# ASD2116.net
KiCad netlist of a schematic drawn in EAGLE
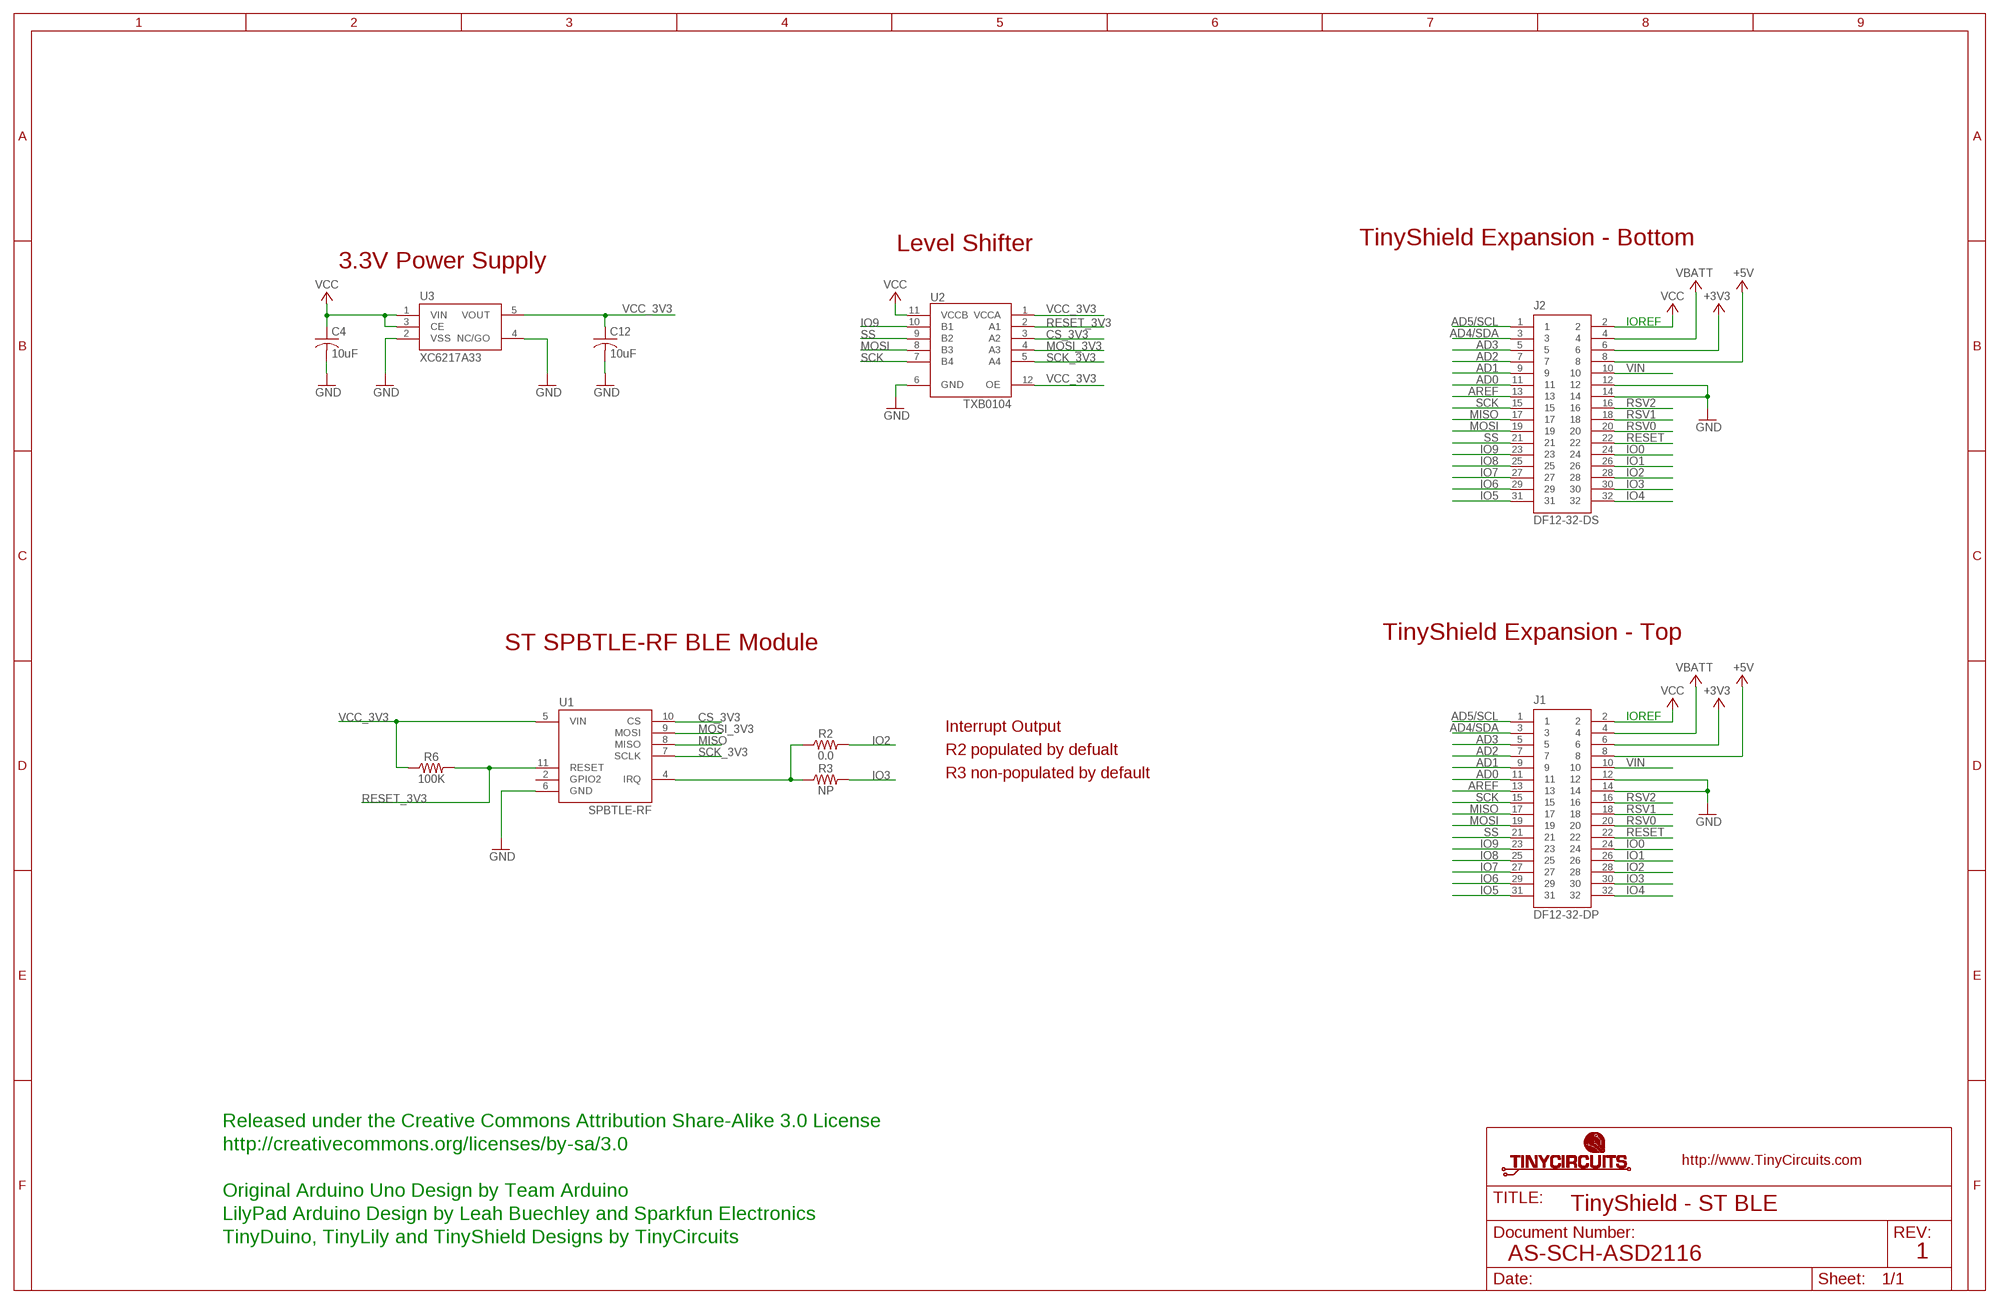
[diagram p0: schematic, sheet 1]

(export (version "E")
  (design (tool "Eeschema 10.0.6"))
  (components
    (comp (ref "C4")
      (value "10uF")
      (footprint "eagle-import:C0603")
      (fields (field (name "PARTNO") "AS-ITM-00002") (field (name "PARTNO_1") "AS-ITM-00002"))
      (libsource (lib "eagle-import") (part "AS-ITM-00002"))
    )
    (comp (ref "C12")
      (value "10uF")
      (footprint "eagle-import:C0603")
      (fields (field (name "PARTNO") "AS-ITM-00002") (field (name "PARTNO_1") "AS-ITM-00002"))
      (libsource (lib "eagle-import") (part "AS-ITM-00002"))
    )
    (comp (ref "J1")
      (value "DF12-32-DP")
      (footprint "eagle-import:DF12-32-DP")
      (fields (field (name "PARTNO") "AS-ITM-00015") (field (name "PARTNO_1") "AS-ITM-00015"))
      (libsource (lib "eagle-import") (part "AS-ITM-00015"))
    )
    (comp (ref "J2")
      (value "DF12-32-DS")
      (footprint "eagle-import:DF12-32-DS")
      (fields (field (name "PARTNO") "AS-ITM-00012") (field (name "PARTNO_1") "AS-ITM-00012"))
      (libsource (lib "eagle-import") (part "AS-ITM-00012"))
    )
    (comp (ref "R2")
      (value "0.0")
      (footprint "eagle-import:0402")
      (fields (field (name "PARTNO") "AS-ITM-00076") (field (name "PARTNO_1") "AS-ITM-00076"))
      (libsource (lib "eagle-import") (part "AS-ITM-00076"))
    )
    (comp (ref "R3")
      (value "NP")
      (footprint "eagle-import:0402")
      (fields (field (name "PARTNO") "AS-ITM-00076") (field (name "PARTNO_1") "AS-ITM-00076"))
      (libsource (lib "eagle-import") (part "AS-ITM-00076"))
    )
    (comp (ref "R6")
      (value "100K")
      (footprint "eagle-import:0402")
      (fields (field (name "PARTNO") "AS-ITM-00004"))
      (libsource (lib "eagle-import") (part "AS-ITM-00004"))
    )
    (comp (ref "U1")
      (value "SPBTLE-RF")
      (footprint "eagle-import:SPBTLE-RF")
      (fields (field (name "PARTNO") "AS-ITM-00294"))
      (libsource (lib "eagle-import") (part "AS-ITM-00294"))
    )
    (comp (ref "U2")
      (value "TXB0104")
      (footprint "eagle-import:UQFN-12")
      (fields (field (name "PARTNO") "AS-ITM-00048"))
      (libsource (lib "eagle-import") (part "AS-ITM-00048"))
    )
    (comp (ref "U3")
      (value "XC6217A33")
      (footprint "eagle-import:SOT-25")
      (fields (field (name "PARTNO") "AS-ITM-00249") (field (name "PARTNO_1") "AS-ITM-00249"))
      (libsource (lib "eagle-import") (part "AS-ITM-00249"))
    )
  )
  (nets
    (net (code "1") (name "+3V3") (class "Default")
      (node (ref "J1") (pin "6") (pinfunction "6_6") (pintype "bidirectional"))
      (node (ref "J2") (pin "6") (pinfunction "6_6") (pintype "bidirectional"))
    )
    (net (code "2") (name "+5V") (class "Default")
      (node (ref "J1") (pin "8") (pinfunction "8_8") (pintype "bidirectional"))
      (node (ref "J2") (pin "8") (pinfunction "8_8") (pintype "bidirectional"))
    )
    (net (code "3") (name "/AD0") (class "Default")
      (node (ref "J1") (pin "11") (pinfunction "11_11") (pintype "bidirectional"))
      (node (ref "J2") (pin "11") (pinfunction "11_11") (pintype "bidirectional"))
    )
    (net (code "4") (name "/AD1") (class "Default")
      (node (ref "J1") (pin "9") (pinfunction "9_9") (pintype "bidirectional"))
      (node (ref "J2") (pin "9") (pinfunction "9_9") (pintype "bidirectional"))
    )
    (net (code "5") (name "/AD2") (class "Default")
      (node (ref "J1") (pin "7") (pinfunction "7_7") (pintype "bidirectional"))
      (node (ref "J2") (pin "7") (pinfunction "7_7") (pintype "bidirectional"))
    )
    (net (code "6") (name "/AD3") (class "Default")
      (node (ref "J1") (pin "5") (pinfunction "5_5") (pintype "bidirectional"))
      (node (ref "J2") (pin "5") (pinfunction "5_5") (pintype "bidirectional"))
    )
    (net (code "7") (name "/AD4{slash}SDA") (class "Default")
      (node (ref "J1") (pin "3") (pinfunction "3_3") (pintype "bidirectional"))
      (node (ref "J2") (pin "3") (pinfunction "3_3") (pintype "bidirectional"))
    )
    (net (code "8") (name "/AD5{slash}SCL") (class "Default")
      (node (ref "J1") (pin "1") (pinfunction "1_1") (pintype "bidirectional"))
      (node (ref "J2") (pin "1") (pinfunction "1_1") (pintype "bidirectional"))
    )
    (net (code "9") (name "/AREF") (class "Default")
      (node (ref "J1") (pin "13") (pinfunction "13_13") (pintype "bidirectional"))
      (node (ref "J2") (pin "13") (pinfunction "13_13") (pintype "bidirectional"))
    )
    (net (code "10") (name "/CS_3V3") (class "Default")
      (node (ref "U1") (pin "10") (pinfunction "CS_10") (pintype "bidirectional"))
      (node (ref "U2") (pin "3") (pinfunction "A2_3") (pintype "bidirectional"))
    )
    (net (code "11") (name "/IO0") (class "Default")
      (node (ref "J1") (pin "24") (pinfunction "24_24") (pintype "bidirectional"))
      (node (ref "J2") (pin "24") (pinfunction "24_24") (pintype "bidirectional"))
    )
    (net (code "12") (name "/IO1") (class "Default")
      (node (ref "J1") (pin "26") (pinfunction "26_26") (pintype "bidirectional"))
      (node (ref "J2") (pin "26") (pinfunction "26_26") (pintype "bidirectional"))
    )
    (net (code "13") (name "/IO2") (class "Default")
      (node (ref "J1") (pin "28") (pinfunction "28_28") (pintype "bidirectional"))
      (node (ref "J2") (pin "28") (pinfunction "28_28") (pintype "bidirectional"))
      (node (ref "R2") (pin "2") (pinfunction "2_2") (pintype "passive"))
    )
    (net (code "14") (name "/IO3") (class "Default")
      (node (ref "J1") (pin "30") (pinfunction "30_30") (pintype "bidirectional"))
      (node (ref "J2") (pin "30") (pinfunction "30_30") (pintype "bidirectional"))
      (node (ref "R3") (pin "2") (pinfunction "2_2") (pintype "passive"))
    )
    (net (code "15") (name "/IO4") (class "Default")
      (node (ref "J1") (pin "32") (pinfunction "32_32") (pintype "bidirectional"))
      (node (ref "J2") (pin "32") (pinfunction "32_32") (pintype "bidirectional"))
    )
    (net (code "16") (name "/IO5") (class "Default")
      (node (ref "J1") (pin "31") (pinfunction "31_31") (pintype "bidirectional"))
      (node (ref "J2") (pin "31") (pinfunction "31_31") (pintype "bidirectional"))
    )
    (net (code "17") (name "/IO6") (class "Default")
      (node (ref "J1") (pin "29") (pinfunction "29_29") (pintype "bidirectional"))
      (node (ref "J2") (pin "29") (pinfunction "29_29") (pintype "bidirectional"))
    )
    (net (code "18") (name "/IO7") (class "Default")
      (node (ref "J1") (pin "27") (pinfunction "27_27") (pintype "bidirectional"))
      (node (ref "J2") (pin "27") (pinfunction "27_27") (pintype "bidirectional"))
    )
    (net (code "19") (name "/IO8") (class "Default")
      (node (ref "J1") (pin "25") (pinfunction "25_25") (pintype "bidirectional"))
      (node (ref "J2") (pin "25") (pinfunction "25_25") (pintype "bidirectional"))
    )
    (net (code "20") (name "/IO9") (class "Default")
      (node (ref "J1") (pin "23") (pinfunction "23_23") (pintype "bidirectional"))
      (node (ref "J2") (pin "23") (pinfunction "23_23") (pintype "bidirectional"))
      (node (ref "U2") (pin "10") (pinfunction "B1_10") (pintype "bidirectional"))
    )
    (net (code "21") (name "/MISO") (class "Default")
      (node (ref "J1") (pin "17") (pinfunction "17_17") (pintype "bidirectional"))
      (node (ref "J2") (pin "17") (pinfunction "17_17") (pintype "bidirectional"))
      (node (ref "U1") (pin "8") (pinfunction "MISO_8") (pintype "bidirectional"))
    )
    (net (code "22") (name "/MOSI") (class "Default")
      (node (ref "J1") (pin "19") (pinfunction "19_19") (pintype "bidirectional"))
      (node (ref "J2") (pin "19") (pinfunction "19_19") (pintype "bidirectional"))
      (node (ref "U2") (pin "8") (pinfunction "B3_8") (pintype "bidirectional"))
    )
    (net (code "23") (name "/MOSI_3V3") (class "Default")
      (node (ref "U1") (pin "9") (pinfunction "MOSI_9") (pintype "bidirectional"))
      (node (ref "U2") (pin "4") (pinfunction "A3_4") (pintype "bidirectional"))
    )
    (net (code "24") (name "/RESET") (class "Default")
      (node (ref "J1") (pin "22") (pinfunction "22_22") (pintype "bidirectional"))
      (node (ref "J2") (pin "22") (pinfunction "22_22") (pintype "bidirectional"))
    )
    (net (code "25") (name "/RESET_3V3") (class "Default")
      (node (ref "R6") (pin "2") (pinfunction "2_2") (pintype "passive"))
      (node (ref "U1") (pin "11") (pinfunction "RESET_11") (pintype "bidirectional"))
      (node (ref "U2") (pin "2") (pinfunction "A1_2") (pintype "bidirectional"))
    )
    (net (code "26") (name "/RSV0") (class "Default")
      (node (ref "J1") (pin "20") (pinfunction "20_20") (pintype "bidirectional"))
      (node (ref "J2") (pin "20") (pinfunction "20_20") (pintype "bidirectional"))
    )
    (net (code "27") (name "/RSV1") (class "Default")
      (node (ref "J1") (pin "18") (pinfunction "18_18") (pintype "bidirectional"))
      (node (ref "J2") (pin "18") (pinfunction "18_18") (pintype "bidirectional"))
    )
    (net (code "28") (name "/RSV2") (class "Default")
      (node (ref "J1") (pin "16") (pinfunction "16_16") (pintype "bidirectional"))
      (node (ref "J2") (pin "16") (pinfunction "16_16") (pintype "bidirectional"))
    )
    (net (code "29") (name "/SCK") (class "Default")
      (node (ref "J1") (pin "15") (pinfunction "15_15") (pintype "bidirectional"))
      (node (ref "J2") (pin "15") (pinfunction "15_15") (pintype "bidirectional"))
      (node (ref "U2") (pin "7") (pinfunction "B4_7") (pintype "bidirectional"))
    )
    (net (code "30") (name "/SCK_3V3") (class "Default")
      (node (ref "U1") (pin "7") (pinfunction "SCLK_7") (pintype "bidirectional"))
      (node (ref "U2") (pin "5") (pinfunction "A4_5") (pintype "bidirectional"))
    )
    (net (code "31") (name "/SS") (class "Default")
      (node (ref "J1") (pin "21") (pinfunction "21_21") (pintype "bidirectional"))
      (node (ref "J2") (pin "21") (pinfunction "21_21") (pintype "bidirectional"))
      (node (ref "U2") (pin "9") (pinfunction "B2_9") (pintype "bidirectional"))
    )
    (net (code "32") (name "/VCC_3V3") (class "Default")
      (node (ref "C12") (pin "1") (pinfunction "1_1") (pintype "passive"))
      (node (ref "R6") (pin "1") (pinfunction "1_1") (pintype "passive"))
      (node (ref "U1") (pin "5") (pinfunction "VIN_5") (pintype "bidirectional"))
      (node (ref "U2") (pin "1") (pinfunction "VCCA_1") (pintype "bidirectional"))
      (node (ref "U2") (pin "12") (pinfunction "OE_12") (pintype "bidirectional"))
      (node (ref "U3") (pin "5") (pinfunction "VOUT_5") (pintype "bidirectional"))
    )
    (net (code "33") (name "/VIN") (class "Default")
      (node (ref "J1") (pin "10") (pinfunction "10_10") (pintype "bidirectional"))
      (node (ref "J2") (pin "10") (pinfunction "10_10") (pintype "bidirectional"))
    )
    (net (code "34") (name "GND") (class "Default")
      (node (ref "C12") (pin "2") (pinfunction "2_2") (pintype "passive"))
      (node (ref "C4") (pin "2") (pinfunction "2_2") (pintype "passive"))
      (node (ref "J1") (pin "12") (pinfunction "12_12") (pintype "bidirectional"))
      (node (ref "J1") (pin "14") (pinfunction "14_14") (pintype "bidirectional"))
      (node (ref "J2") (pin "12") (pinfunction "12_12") (pintype "bidirectional"))
      (node (ref "J2") (pin "14") (pinfunction "14_14") (pintype "bidirectional"))
      (node (ref "U1") (pin "6") (pinfunction "GND_6") (pintype "bidirectional"))
      (node (ref "U2") (pin "6") (pinfunction "GND_6") (pintype "bidirectional"))
      (node (ref "U3") (pin "2") (pinfunction "VSS_2") (pintype "power_in"))
      (node (ref "U3") (pin "4") (pinfunction "NC/GO_4") (pintype "bidirectional"))
    )
    (net (code "35") (name "Net-(U1-IRQ)") (class "Default")
      (node (ref "R2") (pin "1") (pinfunction "1_1") (pintype "passive"))
      (node (ref "R3") (pin "1") (pinfunction "1_1") (pintype "passive"))
      (node (ref "U1") (pin "4") (pinfunction "IRQ_4") (pintype "bidirectional"))
    )
    (net (code "36") (name "VBATT") (class "Default")
      (node (ref "J1") (pin "4") (pinfunction "4_4") (pintype "bidirectional"))
      (node (ref "J2") (pin "4") (pinfunction "4_4") (pintype "bidirectional"))
    )
    (net (code "37") (name "VCC") (class "Default")
      (node (ref "C4") (pin "1") (pinfunction "1_1") (pintype "passive"))
      (node (ref "J1") (pin "2") (pinfunction "2_2") (pintype "bidirectional"))
      (node (ref "J2") (pin "2") (pinfunction "2_2") (pintype "bidirectional"))
      (node (ref "U2") (pin "11") (pinfunction "VCCB_11") (pintype "bidirectional"))
      (node (ref "U3") (pin "1") (pinfunction "VIN_1") (pintype "bidirectional"))
      (node (ref "U3") (pin "3") (pinfunction "CE_3") (pintype "bidirectional"))
    )
    (net (code "38") (name "unconnected-(U1-GPIO2-Pad2)") (class "Default")
      (node (ref "U1") (pin "2") (pinfunction "GPIO2_2") (pintype "bidirectional"))
    )
  )
)
